# Schematic.net
KiCad netlist of a schematic drawn in Altium Designer
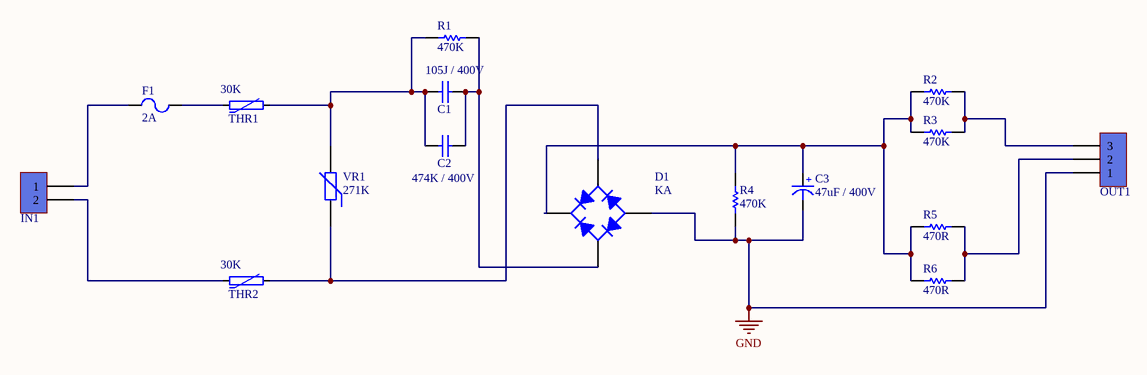
[diagram p0: Schematic.SchDoc]

(export (version "E")
  (design (tool "Eeschema 10.0.6"))
  (components
    (comp (ref "C1")
      (value "105J / 400V")
      (footprint "CBB22")
      (description "Polypropylene film with epoxy Cap CBB22 105J400V")
      (fields (field (name "MANUFACTURER") "CHINA") (field (name "DESIGNER") "Abbas Basereh"))
      (libsource (lib "General 1") (part "Cap CBB22 105J400V"))
    )
    (comp (ref "C2")
      (value "474K / 400V")
      (footprint "CBB22")
      (description "Polypropylene film with epoxy Cap CBB22 105J400V")
      (fields (field (name "MANUFACTURER") "CHINA") (field (name "DESIGNER") "Abbas Basereh"))
      (libsource (lib "General 1") (part "Cap CBB22 105J400V"))
    )
    (comp (ref "C3")
      (value "47uF / 400V")
      (footprint "ELEC-CAP-RAD40-85")
      (description "Electrolytic Capacitor")
      (libsource (lib "AltiumLib1") (part "Capacitor Electrolytic"))
    )
    (comp (ref "D1")
      (value "Bridge Diode")
      (footprint "GBJ")
      (description "Full Wave Bridge Diode")
      (fields (field (name "MODEL") "KA"))
      (libsource (lib "AltiumLib1") (part "Bridge Diode"))
    )
    (comp (ref "F1")
      (value "2A")
      (footprint "FUSE-Double PAD")
      (description "Fuse")
      (libsource (lib "AltiumLib1") (part "Fuse"))
    )
    (comp (ref "IN1")
      (value "KF301_Terminal")
      (footprint "KF301 2PIN")
      (description "Terminal 2 Pin 250VAC 16A")
      (fields (field (name "DESIGNER") "Abbas Basereh"))
      (libsource (lib "Altium") (part "KF301-2Pin_Terminal"))
    )
    (comp (ref "OUT1")
      (value "KF301-3Pin Terminal")
      (footprint "KF301 3PIN")
      (description "Terminal 3 Pin 250VAC 16A")
      (fields (field (name "DESIGNER") "Abbas Basereh"))
      (libsource (lib "2017AbbasBasereh9365731239 -ver1") (part "KF301-3Pin Terminal"))
    )
    (comp (ref "R1")
      (value "470K")
      (footprint "Axial 1W  7_0mm")
      (description "RES Axial 1W")
      (fields (field (name "DESIGNER") "Abbas Basereh"))
      (libsource (lib "2017AbbasBasereh9365731239 -ver1") (part "RES Axial 1W"))
    )
    (comp (ref "R2")
      (value "470K")
      (footprint "Axial 1W  7_0mm")
      (description "RES Axial 1W")
      (fields (field (name "DESIGNER") "Abbas Basereh"))
      (libsource (lib "2017AbbasBasereh9365731239 -ver1") (part "RES Axial 1W"))
    )
    (comp (ref "R3")
      (value "470K")
      (footprint "Axial 1W  7_0mm")
      (description "RES Axial 1W")
      (fields (field (name "DESIGNER") "Abbas Basereh"))
      (libsource (lib "2017AbbasBasereh9365731239 -ver1") (part "RES Axial 1W"))
    )
    (comp (ref "R4")
      (value "470K")
      (footprint "Axial 1W  7_0mm")
      (description "RES Axial 1W")
      (fields (field (name "DESIGNER") "Abbas Basereh"))
      (libsource (lib "2017AbbasBasereh9365731239 -ver1") (part "RES Axial 1W"))
    )
    (comp (ref "R5")
      (value "470R")
      (footprint "Axial 3W 9_0mm")
      (description "RES Axial 3W")
      (fields (field (name "DESIGNER") "Abbas Basereh"))
      (libsource (lib "2017AbbasBasereh9365731239 -ver1") (part "RES Axial 3W"))
    )
    (comp (ref "R6")
      (value "470R")
      (footprint "Axial 3W 9_0mm")
      (description "RES Axial 3W")
      (fields (field (name "DESIGNER") "Abbas Basereh"))
      (libsource (lib "2017AbbasBasereh9365731239 -ver1") (part "RES Axial 3W"))
    )
    (comp (ref "THR1")
      (value "30K")
      (footprint "NTC_10mm")
      (description "NTC")
      (libsource (lib "AltiumLib1 (1)") (part "NTC"))
    )
    (comp (ref "THR2")
      (value "30K")
      (footprint "NTC_10mm")
      (description "NTC")
      (libsource (lib "AltiumLib1 (1)") (part "NTC"))
    )
    (comp (ref "VR1")
      (value "271K")
      (footprint "20D XXX")
      (description "VARISTORS")
      (fields
        (field (name "MANUFACTURER") "china-canada-philipina")
        (field (name "DESIGNER") "Abbas Basereh")
        (field (name "PUBLISHER") "ABBAS BASEREH")
      )
      (libsource (lib "2017AbbasBasereh9365731239 -ver1") (part "VARISTOR (VDR)"))
    )
  )
  (nets
    (net (code "1") (name "GND") (class "Default")
      (node (ref "C3") (pin "1") (pinfunction "-_1") (pintype "passive"))
      (node (ref "D1") (pin "3") (pinfunction "A_3") (pintype "passive"))
      (node (ref "OUT1") (pin "1") (pinfunction "1_1") (pintype "passive"))
      (node (ref "R4") (pin "2") (pinfunction "2_2") (pintype "passive"))
    )
    (net (code "2") (name "Net-(C1-Pad1)") (class "Default")
      (node (ref "C1") (pin "1") (pinfunction "1_1") (pintype "passive"))
      (node (ref "C2") (pin "1") (pinfunction "1_1") (pintype "passive"))
      (node (ref "R1") (pin "1") (pinfunction "1_1") (pintype "passive"))
      (node (ref "THR1") (pin "2") (pinfunction "2_2") (pintype "passive"))
      (node (ref "VR1") (pin "2") (pinfunction "2_2") (pintype "passive"))
    )
    (net (code "3") (name "Net-(C1-Pad2)") (class "Default")
      (node (ref "C1") (pin "2") (pinfunction "2_2") (pintype "passive"))
      (node (ref "C2") (pin "2") (pinfunction "2_2") (pintype "passive"))
      (node (ref "D1") (pin "2") (pinfunction "C_2") (pintype "passive"))
      (node (ref "R1") (pin "2") (pinfunction "2_2") (pintype "passive"))
    )
    (net (code "4") (name "Net-(C3-+)") (class "Default")
      (node (ref "C3") (pin "2") (pinfunction "+_2") (pintype "passive"))
      (node (ref "D1") (pin "1") (pinfunction "K_1") (pintype "passive"))
      (node (ref "R2") (pin "1") (pinfunction "1_1") (pintype "passive"))
      (node (ref "R3") (pin "1") (pinfunction "1_1") (pintype "passive"))
      (node (ref "R4") (pin "1") (pinfunction "1_1") (pintype "passive"))
      (node (ref "R5") (pin "1") (pinfunction "1_1") (pintype "passive"))
      (node (ref "R6") (pin "1") (pinfunction "1_1") (pintype "passive"))
    )
    (net (code "5") (name "Net-(D1-C-Pad4)") (class "Default")
      (node (ref "D1") (pin "4") (pinfunction "C_4") (pintype "passive"))
      (node (ref "THR2") (pin "2") (pinfunction "2_2") (pintype "passive"))
      (node (ref "VR1") (pin "1") (pinfunction "1_1") (pintype "passive"))
    )
    (net (code "6") (name "Net-(F1-Pad1)") (class "Default")
      (node (ref "F1") (pin "1") (pinfunction "1_1") (pintype "passive"))
      (node (ref "IN1") (pin "1") (pinfunction "1_1") (pintype "passive"))
    )
    (net (code "7") (name "Net-(F1-Pad2)") (class "Default")
      (node (ref "F1") (pin "2") (pinfunction "2_2") (pintype "passive"))
      (node (ref "THR1") (pin "1") (pinfunction "1_1") (pintype "passive"))
    )
    (net (code "8") (name "Net-(IN1-Pad2)") (class "Default")
      (node (ref "IN1") (pin "2") (pinfunction "2_2") (pintype "passive"))
      (node (ref "THR2") (pin "1") (pinfunction "1_1") (pintype "passive"))
    )
    (net (code "9") (name "Net-(OUT1-Pad2)") (class "Default")
      (node (ref "OUT1") (pin "2") (pinfunction "2_2") (pintype "passive"))
      (node (ref "R5") (pin "2") (pinfunction "2_2") (pintype "passive"))
      (node (ref "R6") (pin "2") (pinfunction "2_2") (pintype "passive"))
    )
    (net (code "10") (name "Net-(OUT1-Pad3)") (class "Default")
      (node (ref "OUT1") (pin "3") (pinfunction "3_3") (pintype "passive"))
      (node (ref "R2") (pin "2") (pinfunction "2_2") (pintype "passive"))
      (node (ref "R3") (pin "2") (pinfunction "2_2") (pintype "passive"))
    )
  )
)
